# main_controller.net
KiCad netlist of a schematic drawn in Altium Designer
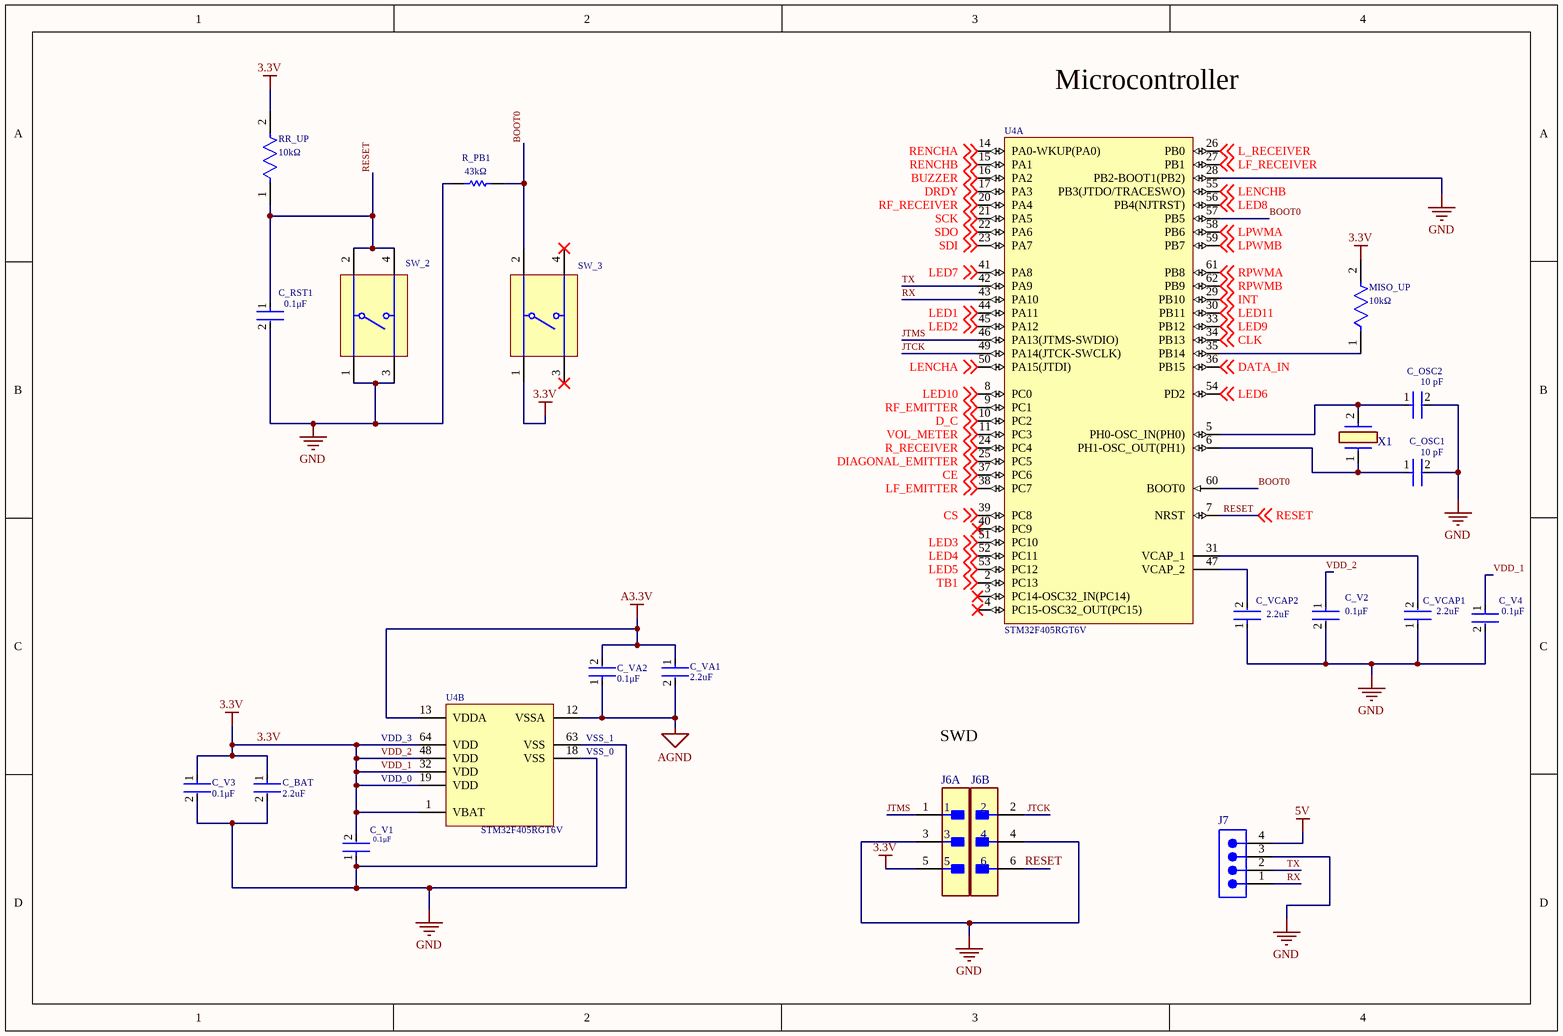
[diagram p0: main_controller.SchDoc]

(export (version "E")
  (design (tool "Eeschema 10.0.6"))
  (components
    (comp (ref "C_BAT")
      (value "C2012X5R1H225K125AB")
      (footprint "FP-C2012-125-0_2-IPC_C")
      (description "Multilayer Ceramic Capacitors 2.2μF ±10% 50V X5R SMD 0805")
      (fields (field (name "TOLERANCE") "10%") (field (name "CAPACITANCE") "2.2uF"))
      (libsource (lib "Altium Content Vault") (part "b4654b650e69147ec39a6b967a45e02"))
    )
    (comp (ref "C_OSC1")
      (value "10 pF")
      (footprint "FP-C0805C-DN-MFG")
      (description "CAP CER 10PF 50V 10% NP0 0805")
      (fields
        (field (name "MANUFACTURER PART NUMBER") "C0805C100K5GACTU")
        (field (name "MANUFACTURER") "KEMET")
      )
      (libsource (lib "Altium Content Vault") (part "b4654b650e69147ec39a6b967a45e02"))
    )
    (comp (ref "C_OSC2")
      (value "10 pF")
      (footprint "FP-C0805C-DN-MFG")
      (description "CAP CER 10PF 50V 10% NP0 0805")
      (fields
        (field (name "MANUFACTURER PART NUMBER") "C0805C100K5GACTU")
        (field (name "MANUFACTURER") "KEMET")
      )
      (libsource (lib "Altium Content Vault") (part "b4654b650e69147ec39a6b967a45e02"))
    )
    (comp (ref "C_RST1")
      (value "0.1μF")
      (footprint "FP-C0805C-DN-MFG")
      (description "CAP CER 0.1UF 10V 5% X7R 0805")
      (fields (field (name "MANUFACTURER") "KEMET") (field (name "TOLERANCE") "0.05"))
      (libsource (lib "Altium Content Vault") (part "b4654b650e69147ec39a6b967a45e02"))
    )
    (comp (ref "C_V1")
      (value "0.1μF")
      (footprint "FP-C0805C-DN-MFG")
      (description "CAP CER 0.1UF 10V 5% X7R 0805")
      (fields (field (name "MANUFACTURER") "KEMET") (field (name "TOLERANCE") "0.05"))
      (libsource (lib "Altium Content Vault") (part "b4654b650e69147ec39a6b967a45e02"))
    )
    (comp (ref "C_V2")
      (value "0.1μF")
      (footprint "FP-C0805C-DN-MFG")
      (description "CAP CER 0.1UF 10V 5% X7R 0805")
      (fields (field (name "MANUFACTURER") "KEMET") (field (name "TOLERANCE") "0.05"))
      (libsource (lib "Altium Content Vault") (part "b4654b650e69147ec39a6b967a45e02"))
    )
    (comp (ref "C_V3")
      (value "0.1μF")
      (footprint "FP-C0805C-DN-MFG")
      (description "CAP CER 0.1UF 10V 5% X7R 0805")
      (fields (field (name "MANUFACTURER") "KEMET") (field (name "TOLERANCE") "0.05"))
      (libsource (lib "Altium Content Vault") (part "b4654b650e69147ec39a6b967a45e02"))
    )
    (comp (ref "C_V4")
      (value "0.1μF")
      (footprint "FP-C0805C-DN-MFG")
      (description "CAP CER 0.1UF 10V 5% X7R 0805")
      (fields (field (name "MANUFACTURER") "KEMET") (field (name "TOLERANCE") "0.05"))
      (libsource (lib "Altium Content Vault") (part "b4654b650e69147ec39a6b967a45e02"))
    )
    (comp (ref "C_VA1")
      (value "C2012X5R1H225K125AB")
      (footprint "FP-C2012-125-0_2-IPC_C")
      (description "Multilayer Ceramic Capacitors 2.2μF ±10% 50V X5R SMD 0805")
      (fields (field (name "TOLERANCE") "10%") (field (name "CAPACITANCE") "2.2uF"))
      (libsource (lib "Altium Content Vault") (part "b4654b650e69147ec39a6b967a45e02"))
    )
    (comp (ref "C_VA2")
      (value "0.1μF")
      (footprint "FP-C0805C-DN-MFG")
      (description "CAP CER 0.1UF 10V 5% X7R 0805")
      (fields (field (name "MANUFACTURER") "KEMET") (field (name "TOLERANCE") "0.05"))
      (libsource (lib "Altium Content Vault") (part "b4654b650e69147ec39a6b967a45e02"))
    )
    (comp (ref "C_VCAP1")
      (value "C2012X5R1H225K125AB")
      (footprint "FP-C2012-125-0_2-IPC_C")
      (description "Multilayer Ceramic Capacitors 2.2μF ±10% 50V X5R SMD 0805")
      (fields (field (name "TOLERANCE") "10%") (field (name "CAPACITANCE") "2.2uF"))
      (libsource (lib "Altium Content Vault") (part "b4654b650e69147ec39a6b967a45e02"))
    )
    (comp (ref "C_VCAP2")
      (value "C2012X5R1H225K125AB")
      (footprint "FP-C2012-125-0_2-IPC_C")
      (description "Multilayer Ceramic Capacitors 2.2μF ±10% 50V X5R SMD 0805")
      (fields (field (name "TOLERANCE") "10%") (field (name "CAPACITANCE") "2.2uF"))
      (libsource (lib "Altium Content Vault") (part "b4654b650e69147ec39a6b967a45e02"))
    )
    (comp (ref "J6")
      (value "90131-0763")
      (footprint "FP-90131-0763-MFG")
      (description "90131-0763 Conn Unshrouded Header HDR 6 POS 2.54mm Solder ST Top Entry Thru-Hole C-Grid III™ Tray")
      (libsource (lib "Altium Content Vault") (part "2654a11fb13586ecb194516b1c997bc"))
    )
    (comp (ref "J7")
      (value "61300411121")
      (footprint "61300411121")
      (libsource (lib "Altium Content Vault") (part "Header_Male_1R_04P"))
    )
    (comp (ref "MISO_UP")
      (value "10kΩ")
      (footprint "FP-ERA3A-IPC_C")
      (description "RES SMD 10K OHM 0.1% 1/10W 0603")
      (fields (field (name "TOLERANCE") "0.1%") (field (name "Comment") "ERA-3AEB103V"))
      (libsource (lib "Altium Content Vault") (part "4e5f8b3dd332802e91518312df5df73"))
    )
    (comp (ref "RR_UP")
      (value "10kΩ")
      (footprint "FP-ERA3A-IPC_C")
      (description "RES SMD 10K OHM 0.1% 1/10W 0603")
      (fields (field (name "TOLERANCE") "0.1%") (field (name "Comment") "ERA-3AEB103V"))
      (libsource (lib "Altium Content Vault") (part "4e5f8b3dd332802e91518312df5df73"))
    )
    (comp (ref "R_PB1")
      (value "43kΩ")
      (footprint "RESC1608X55X30NL20T20")
      (fields (field (name "PART NUMBER") "ERA3AEB433V") (field (name "MANUFACTURER") "Panasonic"))
      (libsource (lib "Altium Content Vault") (part "RES"))
    )
    (comp (ref "SW_2")
      (value "1825910-6")
      (footprint "TECO-1825910-6_V")
      (description "Tact Switch, SPST-NO, 0.05 A, -35 to 85 degC, 4-Pin THD, RoHS, Bulk")
      (fields (field (name "MANUFACTURER") "TE Connectivity"))
      (libsource (lib "Altium Content Vault") (part "SW-SPST-4_A"))
    )
    (comp (ref "SW_3")
      (value "1825910-6")
      (footprint "TECO-1825910-6_V")
      (description "Tact Switch, SPST-NO, 0.05 A, -35 to 85 degC, 4-Pin THD, RoHS, Bulk")
      (fields (field (name "MANUFACTURER") "TE Connectivity"))
      (libsource (lib "Altium Content Vault") (part "SW-SPST-4_A"))
    )
    (comp (ref "U4")
      (value "STM32F405RGT6V")
      (footprint "STM-LQFP64_V")
      (fields (field (name "MANUFACTURER") "STMicroelectronics"))
      (libsource (lib "Altium Content Vault") (part "MC-ARM-STM32F4X5-SQ64"))
    )
    (comp (ref "X1")
      (value "NX5032GA-16.000M-LN-CD-1")
      (footprint "SamacSys:NX5032GA16000000MHZLNCD1")
      (description "Crystal or Oscillator")
      (fields (field (name "MOUSER PART NUMBER") "344-NX5032GA16MLNCD1"))
      (libsource (lib "*") (part "NX5032GA-16.000M-LN-CD-1"))
    )
  )
  (nets
    (net (code "2") (name "/BOOT0") (class "Default")
      (node (ref "R_PB1") (pin "1") (pinfunction "1_1") (pintype "passive"))
      (node (ref "SW_3") (pin "2") (pinfunction "2_2") (pintype "passive"))
      (node (ref "U4") (pin "57") (pinfunction "PB5_57") (pintype "bidirectional"))
      (node (ref "U4") (pin "60") (pinfunction "BOOT0_60") (pintype "input"))
    )
    (net (code "3") (name "/JTCK") (class "Default")
      (node (ref "J6") (pin "2") (pinfunction "2_2") (pintype "passive"))
      (node (ref "U4") (pin "49") (pinfunction "PA14(JTCK-SWCLK)_49") (pintype "bidirectional"))
    )
    (net (code "4") (name "/JTMS") (class "Default")
      (node (ref "J6") (pin "1") (pinfunction "1_1") (pintype "passive"))
      (node (ref "U4") (pin "46") (pinfunction "PA13(JTMS-SWDIO)_46") (pintype "bidirectional"))
    )
    (net (code "5") (name "/RX") (class "Default")
      (node (ref "J7") (pin "1") (pinfunction "1_1") (pintype "passive"))
      (node (ref "U4") (pin "43") (pinfunction "PA10_43") (pintype "bidirectional"))
    )
    (net (code "6") (name "/TX") (class "Default")
      (node (ref "J7") (pin "2") (pinfunction "2_2") (pintype "passive"))
      (node (ref "U4") (pin "42") (pinfunction "PA9_42") (pintype "bidirectional"))
    )
    (net (code "7") (name "3.3V") (class "Default")
      (node (ref "C_BAT") (pin "1") (pinfunction "1_1") (pintype "passive"))
      (node (ref "C_V1") (pin "2") (pinfunction "2_2") (pintype "passive"))
      (node (ref "C_V2") (pin "1") (pinfunction "1_1") (pintype "passive"))
      (node (ref "C_V3") (pin "1") (pinfunction "1_1") (pintype "passive"))
      (node (ref "C_V4") (pin "1") (pinfunction "1_1") (pintype "passive"))
      (node (ref "J6") (pin "5") (pinfunction "5_5") (pintype "passive"))
      (node (ref "MISO_UP") (pin "2") (pinfunction "2_2") (pintype "passive"))
      (node (ref "RR_UP") (pin "2") (pinfunction "2_2") (pintype "passive"))
      (node (ref "SW_3") (pin "1") (pinfunction "1_1") (pintype "passive"))
      (node (ref "U4") (pin "1") (pinfunction "VBAT_1") (pintype "power_in"))
      (node (ref "U4") (pin "19") (pinfunction "VDD_19") (pintype "power_in"))
      (node (ref "U4") (pin "32") (pinfunction "VDD_32") (pintype "power_in"))
      (node (ref "U4") (pin "48") (pinfunction "VDD_48") (pintype "power_in"))
      (node (ref "U4") (pin "64") (pinfunction "VDD_64") (pintype "power_in"))
    )
    (net (code "8") (name "5V") (class "Default")
      (node (ref "J7") (pin "4") (pinfunction "4_4") (pintype "passive"))
    )
    (net (code "9") (name "A3.3V") (class "Default")
      (node (ref "C_VA1") (pin "1") (pinfunction "1_1") (pintype "passive"))
      (node (ref "C_VA2") (pin "2") (pinfunction "2_2") (pintype "passive"))
      (node (ref "U4") (pin "13") (pinfunction "VDDA_13") (pintype "power_in"))
    )
    (net (code "10") (name "AGND") (class "Default")
      (node (ref "C_VA1") (pin "2") (pinfunction "2_2") (pintype "passive"))
      (node (ref "C_VA2") (pin "1") (pinfunction "1_1") (pintype "passive"))
      (node (ref "U4") (pin "12") (pinfunction "VSSA_12") (pintype "power_in"))
    )
    (net (code "11") (name "BUZZER") (class "Default")
      (node (ref "U4") (pin "16") (pinfunction "PA2_16") (pintype "bidirectional"))
    )
    (net (code "12") (name "CE") (class "Default")
      (node (ref "U4") (pin "37") (pinfunction "PC6_37") (pintype "bidirectional"))
    )
    (net (code "13") (name "CLK") (class "Default")
      (node (ref "U4") (pin "34") (pinfunction "PB13_34") (pintype "bidirectional"))
    )
    (net (code "14") (name "CS") (class "Default")
      (node (ref "U4") (pin "39") (pinfunction "PC8_39") (pintype "bidirectional"))
    )
    (net (code "15") (name "DATA_IN") (class "Default")
      (node (ref "U4") (pin "36") (pinfunction "PB15_36") (pintype "bidirectional"))
    )
    (net (code "16") (name "DIAGONAL_EMITTER") (class "Default")
      (node (ref "U4") (pin "25") (pinfunction "PC5_25") (pintype "bidirectional"))
    )
    (net (code "17") (name "DRDY") (class "Default")
      (node (ref "U4") (pin "17") (pinfunction "PA3_17") (pintype "bidirectional"))
    )
    (net (code "18") (name "D_C") (class "Default")
      (node (ref "U4") (pin "10") (pinfunction "PC2_10") (pintype "bidirectional"))
    )
    (net (code "19") (name "GND") (class "Default")
      (node (ref "C_BAT") (pin "2") (pinfunction "2_2") (pintype "passive"))
      (node (ref "C_OSC1") (pin "2") (pinfunction "2_2") (pintype "passive"))
      (node (ref "C_OSC2") (pin "2") (pinfunction "2_2") (pintype "passive"))
      (node (ref "C_RST1") (pin "2") (pinfunction "2_2") (pintype "passive"))
      (node (ref "C_V1") (pin "1") (pinfunction "1_1") (pintype "passive"))
      (node (ref "C_V2") (pin "2") (pinfunction "2_2") (pintype "passive"))
      (node (ref "C_V3") (pin "2") (pinfunction "2_2") (pintype "passive"))
      (node (ref "C_V4") (pin "2") (pinfunction "2_2") (pintype "passive"))
      (node (ref "C_VCAP1") (pin "1") (pinfunction "1_1") (pintype "passive"))
      (node (ref "C_VCAP2") (pin "1") (pinfunction "1_1") (pintype "passive"))
      (node (ref "J6") (pin "3") (pinfunction "3_3") (pintype "passive"))
      (node (ref "J6") (pin "4") (pinfunction "4_4") (pintype "passive"))
      (node (ref "J7") (pin "3") (pinfunction "3_3") (pintype "passive"))
      (node (ref "R_PB1") (pin "2") (pinfunction "2_2") (pintype "passive"))
      (node (ref "SW_2") (pin "1") (pinfunction "1_1") (pintype "passive"))
      (node (ref "SW_2") (pin "3") (pinfunction "3_3") (pintype "passive"))
      (node (ref "U4") (pin "18") (pinfunction "VSS_18") (pintype "power_in"))
      (node (ref "U4") (pin "28") (pinfunction "PB2-BOOT1(PB2)_28") (pintype "bidirectional"))
      (node (ref "U4") (pin "63") (pinfunction "VSS_63") (pintype "power_in"))
    )
    (net (code "20") (name "INT") (class "Default")
      (node (ref "U4") (pin "29") (pinfunction "PB10_29") (pintype "bidirectional"))
    )
    (net (code "21") (name "LED1") (class "Default")
      (node (ref "U4") (pin "44") (pinfunction "PA11_44") (pintype "bidirectional"))
    )
    (net (code "22") (name "LED2") (class "Default")
      (node (ref "U4") (pin "45") (pinfunction "PA12_45") (pintype "bidirectional"))
    )
    (net (code "23") (name "LED3") (class "Default")
      (node (ref "U4") (pin "51") (pinfunction "PC10_51") (pintype "bidirectional"))
    )
    (net (code "24") (name "LED4") (class "Default")
      (node (ref "U4") (pin "52") (pinfunction "PC11_52") (pintype "bidirectional"))
    )
    (net (code "25") (name "LED5") (class "Default")
      (node (ref "U4") (pin "53") (pinfunction "PC12_53") (pintype "bidirectional"))
    )
    (net (code "26") (name "LED6") (class "Default")
      (node (ref "U4") (pin "54") (pinfunction "PD2_54") (pintype "bidirectional"))
    )
    (net (code "27") (name "LED7") (class "Default")
      (node (ref "U4") (pin "41") (pinfunction "PA8_41") (pintype "bidirectional"))
    )
    (net (code "28") (name "LED8") (class "Default")
      (node (ref "U4") (pin "56") (pinfunction "PB4(NJTRST)_56") (pintype "bidirectional"))
    )
    (net (code "29") (name "LED9") (class "Default")
      (node (ref "U4") (pin "33") (pinfunction "PB12_33") (pintype "bidirectional"))
    )
    (net (code "30") (name "LED10") (class "Default")
      (node (ref "U4") (pin "8") (pinfunction "PC0_8") (pintype "bidirectional"))
    )
    (net (code "31") (name "LED11") (class "Default")
      (node (ref "U4") (pin "30") (pinfunction "PB11_30") (pintype "bidirectional"))
    )
    (net (code "32") (name "LENCHA") (class "Default")
      (node (ref "U4") (pin "50") (pinfunction "PA15(JTDI)_50") (pintype "bidirectional"))
    )
    (net (code "33") (name "LENCHB") (class "Default")
      (node (ref "U4") (pin "55") (pinfunction "PB3(JTDO/TRACESWO)_55") (pintype "bidirectional"))
    )
    (net (code "34") (name "LF_EMITTER") (class "Default")
      (node (ref "U4") (pin "38") (pinfunction "PC7_38") (pintype "bidirectional"))
    )
    (net (code "35") (name "LF_RECEIVER") (class "Default")
      (node (ref "U4") (pin "27") (pinfunction "PB1_27") (pintype "bidirectional"))
    )
    (net (code "36") (name "LPWMA") (class "Default")
      (node (ref "U4") (pin "58") (pinfunction "PB6_58") (pintype "bidirectional"))
    )
    (net (code "37") (name "LPWMB") (class "Default")
      (node (ref "U4") (pin "59") (pinfunction "PB7_59") (pintype "bidirectional"))
    )
    (net (code "38") (name "L_RECEIVER") (class "Default")
      (node (ref "U4") (pin "26") (pinfunction "PB0_26") (pintype "bidirectional"))
    )
    (net (code "39") (name "Net-(U4A-PB14)") (class "Default")
      (node (ref "MISO_UP") (pin "1") (pinfunction "1_1") (pintype "passive"))
      (node (ref "U4") (pin "35") (pinfunction "PB14_35") (pintype "bidirectional"))
    )
    (net (code "40") (name "Net-(U4A-PH0-OSC_IN(PH0))") (class "Default")
      (node (ref "C_OSC2") (pin "1") (pinfunction "1_1") (pintype "passive"))
      (node (ref "U4") (pin "5") (pinfunction "PH0-OSC_IN(PH0)_5") (pintype "bidirectional"))
      (node (ref "X1") (pin "2") (pinfunction "X2_2") (pintype "passive"))
    )
    (net (code "41") (name "Net-(U4A-PH1-OSC_OUT(PH1))") (class "Default")
      (node (ref "C_OSC1") (pin "1") (pinfunction "1_1") (pintype "passive"))
      (node (ref "U4") (pin "6") (pinfunction "PH1-OSC_OUT(PH1)_6") (pintype "bidirectional"))
      (node (ref "X1") (pin "1") (pinfunction "X1_1") (pintype "passive"))
    )
    (net (code "42") (name "Net-(U4A-VCAP_1)") (class "Default")
      (node (ref "C_VCAP1") (pin "2") (pinfunction "2_2") (pintype "passive"))
      (node (ref "U4") (pin "31") (pinfunction "VCAP_1_31") (pintype "power_in"))
    )
    (net (code "43") (name "Net-(U4A-VCAP_2)") (class "Default")
      (node (ref "C_VCAP2") (pin "2") (pinfunction "2_2") (pintype "passive"))
      (node (ref "U4") (pin "47") (pinfunction "VCAP_2_47") (pintype "power_in"))
    )
    (net (code "44") (name "RENCHA") (class "Default")
      (node (ref "U4") (pin "14") (pinfunction "PA0-WKUP(PA0)_14") (pintype "bidirectional"))
    )
    (net (code "45") (name "RENCHB") (class "Default")
      (node (ref "U4") (pin "15") (pinfunction "PA1_15") (pintype "bidirectional"))
    )
    (net (code "46") (name "RESET") (class "Default")
      (node (ref "C_RST1") (pin "1") (pinfunction "1_1") (pintype "passive"))
      (node (ref "J6") (pin "6") (pinfunction "6_6") (pintype "passive"))
      (node (ref "RR_UP") (pin "1") (pinfunction "1_1") (pintype "passive"))
      (node (ref "SW_2") (pin "2") (pinfunction "2_2") (pintype "passive"))
      (node (ref "SW_2") (pin "4") (pinfunction "4_4") (pintype "passive"))
      (node (ref "U4") (pin "7") (pinfunction "NRST_7") (pintype "bidirectional"))
    )
    (net (code "47") (name "RF_EMITTER") (class "Default")
      (node (ref "U4") (pin "9") (pinfunction "PC1_9") (pintype "bidirectional"))
    )
    (net (code "48") (name "RF_RECEIVER") (class "Default")
      (node (ref "U4") (pin "20") (pinfunction "PA4_20") (pintype "bidirectional"))
    )
    (net (code "49") (name "RPWMA") (class "Default")
      (node (ref "U4") (pin "61") (pinfunction "PB8_61") (pintype "bidirectional"))
    )
    (net (code "50") (name "RPWMB") (class "Default")
      (node (ref "U4") (pin "62") (pinfunction "PB9_62") (pintype "bidirectional"))
    )
    (net (code "51") (name "R_RECEIVER") (class "Default")
      (node (ref "U4") (pin "24") (pinfunction "PC4_24") (pintype "bidirectional"))
    )
    (net (code "52") (name "SCK") (class "Default")
      (node (ref "U4") (pin "21") (pinfunction "PA5_21") (pintype "bidirectional"))
    )
    (net (code "53") (name "SDI") (class "Default")
      (node (ref "U4") (pin "23") (pinfunction "PA7_23") (pintype "bidirectional"))
    )
    (net (code "54") (name "SDO") (class "Default")
      (node (ref "U4") (pin "22") (pinfunction "PA6_22") (pintype "bidirectional"))
    )
    (net (code "55") (name "TB1") (class "Default")
      (node (ref "U4") (pin "2") (pinfunction "PC13_2") (pintype "bidirectional"))
    )
    (net (code "56") (name "VOL_METER") (class "Default")
      (node (ref "U4") (pin "11") (pinfunction "PC3_11") (pintype "bidirectional"))
    )
    (net (code "57") (name "unconnected-(SW_3-Pad3)") (class "Default")
      (node (ref "SW_3") (pin "3") (pinfunction "3_3") (pintype "passive+no_connect"))
    )
    (net (code "58") (name "unconnected-(SW_3-Pad4)") (class "Default")
      (node (ref "SW_3") (pin "4") (pinfunction "4_4") (pintype "passive+no_connect"))
    )
    (net (code "59") (name "unconnected-(U4A-PC9-Pad40)") (class "Default")
      (node (ref "U4") (pin "40") (pinfunction "PC9_40") (pintype "bidirectional+no_connect"))
    )
    (net (code "60") (name "unconnected-(U4A-PC14-OSC32_IN(PC14)-Pad3)") (class "Default")
      (node (ref "U4") (pin "3") (pinfunction "PC14-OSC32_IN(PC14)_3") (pintype "bidirectional+no_connect"))
    )
    (net (code "61") (name "unconnected-(U4A-PC15-OSC32_OUT(PC15)-Pad4)") (class "Default")
      (node (ref "U4") (pin "4") (pinfunction "PC15-OSC32_OUT(PC15)_4") (pintype "bidirectional+no_connect"))
    )
  )
)
